# SuperPro.net
KiCad netlist of a schematic drawn in EAGLE
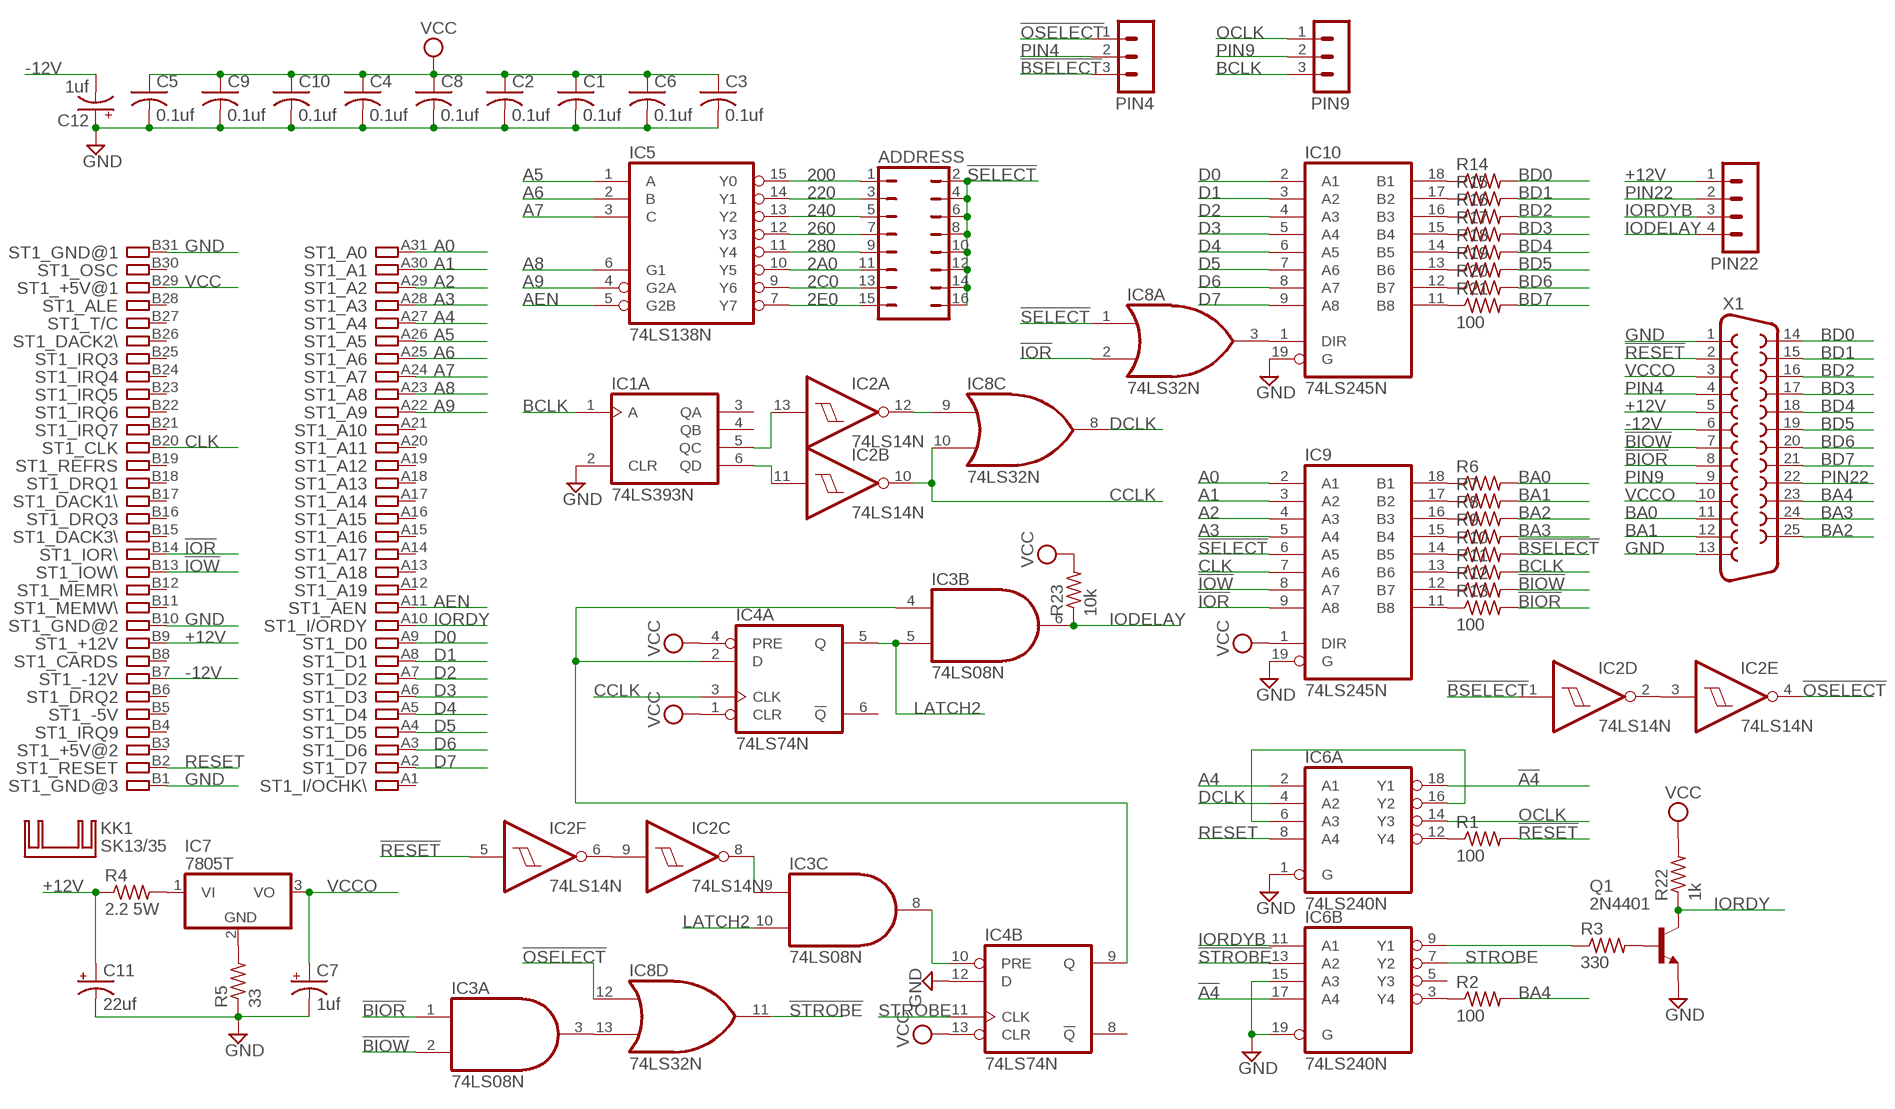
[diagram p0: schematic, sheet 1]

(export (version "E")
  (design (tool "Eeschema 10.0.6"))
  (components
    (comp (ref "ADDRESS")
      (value "JP8Q")
      (footprint "eagle-import:JP8Q")
      (libsource (lib "eagle-import") (part "JP8Q"))
    )
    (comp (ref "C1")
      (value "0.1uf")
      (footprint "eagle-import:C050-025X075")
      (libsource (lib "eagle-import") (part "C-US050-025X075"))
    )
    (comp (ref "C2")
      (value "0.1uf")
      (footprint "eagle-import:C050-025X075")
      (libsource (lib "eagle-import") (part "C-US050-025X075"))
    )
    (comp (ref "C3")
      (value "0.1uf")
      (footprint "eagle-import:C050-025X075")
      (libsource (lib "eagle-import") (part "C-US050-025X075"))
    )
    (comp (ref "C4")
      (value "0.1uf")
      (footprint "eagle-import:C050-025X075")
      (libsource (lib "eagle-import") (part "C-US050-025X075"))
    )
    (comp (ref "C5")
      (value "0.1uf")
      (footprint "eagle-import:C050-025X075")
      (libsource (lib "eagle-import") (part "C-US050-025X075"))
    )
    (comp (ref "C6")
      (value "0.1uf")
      (footprint "eagle-import:C050-025X075")
      (libsource (lib "eagle-import") (part "C-US050-025X075"))
    )
    (comp (ref "C7")
      (value "1uf")
      (footprint "eagle-import:E5-10,5")
      (libsource (lib "eagle-import") (part "CPOL-USE5-10.5"))
    )
    (comp (ref "C8")
      (value "0.1uf")
      (footprint "eagle-import:C050-025X075")
      (libsource (lib "eagle-import") (part "C-US050-025X075"))
    )
    (comp (ref "C9")
      (value "0.1uf")
      (footprint "eagle-import:C050-025X075")
      (libsource (lib "eagle-import") (part "C-US050-025X075"))
    )
    (comp (ref "C10")
      (value "0.1uf")
      (footprint "eagle-import:C050-025X075")
      (libsource (lib "eagle-import") (part "C-US050-025X075"))
    )
    (comp (ref "C11")
      (value "22uf")
      (footprint "eagle-import:E5-10,5")
      (libsource (lib "eagle-import") (part "CPOL-USE5-10.5"))
    )
    (comp (ref "C12")
      (value "1uf")
      (footprint "eagle-import:E5-10,5")
      (libsource (lib "eagle-import") (part "CPOL-USE5-10.5"))
    )
    (comp (ref "IC1")
      (value "74LS393N")
      (footprint "eagle-import:DIL14")
      (libsource (lib "eagle-import") (part "74393NLS"))
    )
    (comp (ref "IC2")
      (value "74LS14N")
      (footprint "eagle-import:DIL14")
      (libsource (lib "eagle-import") (part "7414NLS"))
    )
    (comp (ref "IC3")
      (value "74LS08N")
      (footprint "eagle-import:DIL14")
      (libsource (lib "eagle-import") (part "7408NLS"))
    )
    (comp (ref "IC4")
      (value "74LS74N")
      (footprint "eagle-import:DIL14")
      (libsource (lib "eagle-import") (part "7474NLS"))
    )
    (comp (ref "IC5")
      (value "74LS138N")
      (footprint "eagle-import:DIL16")
      (libsource (lib "eagle-import") (part "74138NLS"))
    )
    (comp (ref "IC6")
      (value "74LS240N")
      (footprint "eagle-import:DIL20")
      (libsource (lib "eagle-import") (part "74240NLS"))
    )
    (comp (ref "IC7")
      (value "7805T")
      (footprint "eagle-import:TO220H")
      (libsource (lib "eagle-import") (part "78T05"))
    )
    (comp (ref "IC8")
      (value "74LS32N")
      (footprint "eagle-import:DIL14")
      (libsource (lib "eagle-import") (part "7432NLS"))
    )
    (comp (ref "IC9")
      (value "74LS245N")
      (footprint "eagle-import:DIL20")
      (libsource (lib "eagle-import") (part "74245NLS"))
    )
    (comp (ref "IC10")
      (value "74LS245N")
      (footprint "eagle-import:DIL20")
      (libsource (lib "eagle-import") (part "74245NLS"))
    )
    (comp (ref "KK1")
      (value "SK13/35")
      (footprint "eagle-import:SK13_35")
      (libsource (lib "eagle-import") (part "SK13/35"))
    )
    (comp (ref "PIN4")
      (value "MA03-1")
      (footprint "eagle-import:MA03-1")
      (libsource (lib "eagle-import") (part "MA03-1"))
    )
    (comp (ref "PIN9")
      (value "MA03-1")
      (footprint "eagle-import:MA03-1")
      (libsource (lib "eagle-import") (part "MA03-1"))
    )
    (comp (ref "PIN22")
      (value "MA04-1")
      (footprint "eagle-import:MA04-1")
      (libsource (lib "eagle-import") (part "MA04-1"))
    )
    (comp (ref "Q1")
      (value "2N4401")
      (footprint "eagle-import:TO92")
      (libsource (lib "eagle-import") (part "2N4416"))
    )
    (comp (ref "R1")
      (value "100")
      (footprint "eagle-import:0207_10")
      (libsource (lib "eagle-import") (part "R-US_0207/10"))
    )
    (comp (ref "R2")
      (value "100")
      (footprint "eagle-import:0207_10")
      (libsource (lib "eagle-import") (part "R-US_0207/10"))
    )
    (comp (ref "R3")
      (value "330")
      (footprint "eagle-import:0207_10")
      (libsource (lib "eagle-import") (part "R-US_0207/10"))
    )
    (comp (ref "R4")
      (value "2.2 5W")
      (footprint "eagle-import:0922_22")
      (libsource (lib "eagle-import") (part "R-US_0922/22"))
    )
    (comp (ref "R5")
      (value "33")
      (footprint "eagle-import:0207_10")
      (libsource (lib "eagle-import") (part "R-US_0207/10"))
    )
    (comp (ref "R6")
      (value "R-US_0207/10")
      (footprint "eagle-import:0207_10")
      (libsource (lib "eagle-import") (part "R-US_0207/10"))
    )
    (comp (ref "R7")
      (value "R-US_0207/10")
      (footprint "eagle-import:0207_10")
      (libsource (lib "eagle-import") (part "R-US_0207/10"))
    )
    (comp (ref "R8")
      (value "R-US_0207/10")
      (footprint "eagle-import:0207_10")
      (libsource (lib "eagle-import") (part "R-US_0207/10"))
    )
    (comp (ref "R9")
      (value "R-US_0207/10")
      (footprint "eagle-import:0207_10")
      (libsource (lib "eagle-import") (part "R-US_0207/10"))
    )
    (comp (ref "R10")
      (value "R-US_0207/10")
      (footprint "eagle-import:0207_10")
      (libsource (lib "eagle-import") (part "R-US_0207/10"))
    )
    (comp (ref "R11")
      (value "R-US_0207/10")
      (footprint "eagle-import:0207_10")
      (libsource (lib "eagle-import") (part "R-US_0207/10"))
    )
    (comp (ref "R12")
      (value "R-US_0207/10")
      (footprint "eagle-import:0207_10")
      (libsource (lib "eagle-import") (part "R-US_0207/10"))
    )
    (comp (ref "R13")
      (value "100")
      (footprint "eagle-import:0207_10")
      (libsource (lib "eagle-import") (part "R-US_0207/10"))
    )
    (comp (ref "R14")
      (value "R-US_0207/10")
      (footprint "eagle-import:0207_10")
      (libsource (lib "eagle-import") (part "R-US_0207/10"))
    )
    (comp (ref "R15")
      (value "R-US_0207/10")
      (footprint "eagle-import:0207_10")
      (libsource (lib "eagle-import") (part "R-US_0207/10"))
    )
    (comp (ref "R16")
      (value "R-US_0207/10")
      (footprint "eagle-import:0207_10")
      (libsource (lib "eagle-import") (part "R-US_0207/10"))
    )
    (comp (ref "R17")
      (value "R-US_0207/10")
      (footprint "eagle-import:0207_10")
      (libsource (lib "eagle-import") (part "R-US_0207/10"))
    )
    (comp (ref "R18")
      (value "R-US_0207/10")
      (footprint "eagle-import:0207_10")
      (libsource (lib "eagle-import") (part "R-US_0207/10"))
    )
    (comp (ref "R19")
      (value "R-US_0207/10")
      (footprint "eagle-import:0207_10")
      (libsource (lib "eagle-import") (part "R-US_0207/10"))
    )
    (comp (ref "R20")
      (value "R-US_0207/10")
      (footprint "eagle-import:0207_10")
      (libsource (lib "eagle-import") (part "R-US_0207/10"))
    )
    (comp (ref "R21")
      (value "100")
      (footprint "eagle-import:0207_10")
      (libsource (lib "eagle-import") (part "R-US_0207/10"))
    )
    (comp (ref "R22")
      (value "1k")
      (footprint "eagle-import:0207_10")
      (libsource (lib "eagle-import") (part "R-US_0207/10"))
    )
    (comp (ref "R23")
      (value "10k")
      (footprint "eagle-import:0207_10")
      (libsource (lib "eagle-import") (part "R-US_0207/10"))
    )
    (comp (ref "ST1")
      (value "IBM8BIT")
      (footprint "eagle-import:IBM8BIT")
      (libsource (lib "eagle-import") (part "IBM8BIT"))
    )
    (comp (ref "X1")
      (value "F25H")
      (footprint "eagle-import:F25H")
      (libsource (lib "eagle-import") (part "F25H"))
    )
  )
  (nets
    (net (code "1") (name "/+12V") (class "Default")
      (node (ref "C11") (pin "+") (pinfunction "+_+") (pintype "passive"))
      (node (ref "PIN22") (pin "1") (pinfunction "1_1") (pintype "passive"))
      (node (ref "R4") (pin "1") (pinfunction "1_1") (pintype "passive"))
      (node (ref "ST1") (pin "B9") (pinfunction "P_B9") (pintype "bidirectional"))
      (node (ref "X1") (pin "5") (pinfunction "5_5") (pintype "passive"))
    )
    (net (code "2") (name "/-12V") (class "Default")
      (node (ref "C12") (pin "-") (pinfunction "-_-") (pintype "passive"))
      (node (ref "ST1") (pin "B7") (pinfunction "P_B7") (pintype "bidirectional"))
      (node (ref "X1") (pin "6") (pinfunction "6_6") (pintype "passive"))
    )
    (net (code "3") (name "/2A0") (class "Default")
      (node (ref "ADDRESS") (pin "11") (pinfunction "11_11") (pintype "passive"))
      (node (ref "IC5") (pin "10") (pinfunction "Y5_10") (pintype "output"))
    )
    (net (code "4") (name "/2C0") (class "Default")
      (node (ref "ADDRESS") (pin "13") (pinfunction "13_13") (pintype "passive"))
      (node (ref "IC5") (pin "9") (pinfunction "Y6_9") (pintype "output"))
    )
    (net (code "5") (name "/2E0") (class "Default")
      (node (ref "ADDRESS") (pin "15") (pinfunction "15_15") (pintype "passive"))
      (node (ref "IC5") (pin "7") (pinfunction "Y7_7") (pintype "output"))
    )
    (net (code "6") (name "/200") (class "Default")
      (node (ref "ADDRESS") (pin "1") (pinfunction "1_1") (pintype "passive"))
      (node (ref "IC5") (pin "15") (pinfunction "Y0_15") (pintype "output"))
    )
    (net (code "7") (name "/220") (class "Default")
      (node (ref "ADDRESS") (pin "3") (pinfunction "3_3") (pintype "passive"))
      (node (ref "IC5") (pin "14") (pinfunction "Y1_14") (pintype "output"))
    )
    (net (code "8") (name "/240") (class "Default")
      (node (ref "ADDRESS") (pin "5") (pinfunction "5_5") (pintype "passive"))
      (node (ref "IC5") (pin "13") (pinfunction "Y2_13") (pintype "output"))
    )
    (net (code "9") (name "/260") (class "Default")
      (node (ref "ADDRESS") (pin "7") (pinfunction "7_7") (pintype "passive"))
      (node (ref "IC5") (pin "12") (pinfunction "Y3_12") (pintype "output"))
    )
    (net (code "10") (name "/280") (class "Default")
      (node (ref "ADDRESS") (pin "9") (pinfunction "9_9") (pintype "passive"))
      (node (ref "IC5") (pin "11") (pinfunction "Y4_11") (pintype "output"))
    )
    (net (code "11") (name "/A0") (class "Default")
      (node (ref "IC9") (pin "2") (pinfunction "A1_2") (pintype "bidirectional"))
      (node (ref "ST1") (pin "A31") (pinfunction "P_A31") (pintype "bidirectional"))
    )
    (net (code "12") (name "/A1") (class "Default")
      (node (ref "IC9") (pin "3") (pinfunction "A2_3") (pintype "bidirectional"))
      (node (ref "ST1") (pin "A30") (pinfunction "P_A30") (pintype "bidirectional"))
    )
    (net (code "13") (name "/A2") (class "Default")
      (node (ref "IC9") (pin "4") (pinfunction "A3_4") (pintype "bidirectional"))
      (node (ref "ST1") (pin "A29") (pinfunction "P_A29") (pintype "bidirectional"))
    )
    (net (code "14") (name "/A3") (class "Default")
      (node (ref "IC9") (pin "5") (pinfunction "A4_5") (pintype "bidirectional"))
      (node (ref "ST1") (pin "A28") (pinfunction "P_A28") (pintype "bidirectional"))
    )
    (net (code "15") (name "/A4") (class "Default")
      (node (ref "IC6") (pin "2") (pinfunction "A1_2") (pintype "input"))
      (node (ref "ST1") (pin "A27") (pinfunction "P_A27") (pintype "bidirectional"))
    )
    (net (code "16") (name "/A5") (class "Default")
      (node (ref "IC5") (pin "1") (pinfunction "A_1") (pintype "input"))
      (node (ref "ST1") (pin "A26") (pinfunction "P_A26") (pintype "bidirectional"))
    )
    (net (code "17") (name "/A6") (class "Default")
      (node (ref "IC5") (pin "2") (pinfunction "B_2") (pintype "input"))
      (node (ref "ST1") (pin "A25") (pinfunction "P_A25") (pintype "bidirectional"))
    )
    (net (code "18") (name "/A7") (class "Default")
      (node (ref "IC5") (pin "3") (pinfunction "C_3") (pintype "input"))
      (node (ref "ST1") (pin "A24") (pinfunction "P_A24") (pintype "bidirectional"))
    )
    (net (code "19") (name "/A8") (class "Default")
      (node (ref "IC5") (pin "6") (pinfunction "G1_6") (pintype "input"))
      (node (ref "ST1") (pin "A23") (pinfunction "P_A23") (pintype "bidirectional"))
    )
    (net (code "20") (name "/A9") (class "Default")
      (node (ref "IC5") (pin "4") (pinfunction "G2A_4") (pintype "input"))
      (node (ref "ST1") (pin "A22") (pinfunction "P_A22") (pintype "bidirectional"))
    )
    (net (code "21") (name "/AEN") (class "Default")
      (node (ref "IC5") (pin "5") (pinfunction "G2B_5") (pintype "input"))
      (node (ref "ST1") (pin "A11") (pinfunction "P_A11") (pintype "bidirectional"))
    )
    (net (code "22") (name "/BA0") (class "Default")
      (node (ref "R6") (pin "2") (pinfunction "2_2") (pintype "passive"))
      (node (ref "X1") (pin "11") (pinfunction "11_11") (pintype "passive"))
    )
    (net (code "23") (name "/BA1") (class "Default")
      (node (ref "R7") (pin "2") (pinfunction "2_2") (pintype "passive"))
      (node (ref "X1") (pin "12") (pinfunction "12_12") (pintype "passive"))
    )
    (net (code "24") (name "/BA2") (class "Default")
      (node (ref "R8") (pin "2") (pinfunction "2_2") (pintype "passive"))
      (node (ref "X1") (pin "25") (pinfunction "25_25") (pintype "passive"))
    )
    (net (code "25") (name "/BA3") (class "Default")
      (node (ref "R9") (pin "2") (pinfunction "2_2") (pintype "passive"))
      (node (ref "X1") (pin "24") (pinfunction "24_24") (pintype "passive"))
    )
    (net (code "26") (name "/BA4") (class "Default")
      (node (ref "R2") (pin "2") (pinfunction "2_2") (pintype "passive"))
      (node (ref "X1") (pin "23") (pinfunction "23_23") (pintype "passive"))
    )
    (net (code "27") (name "/BCLK") (class "Default")
      (node (ref "IC1") (pin "1") (pinfunction "A_1") (pintype "input"))
      (node (ref "PIN9") (pin "3") (pinfunction "3_3") (pintype "passive"))
      (node (ref "R11") (pin "2") (pinfunction "2_2") (pintype "passive"))
    )
    (net (code "28") (name "/BD0") (class "Default")
      (node (ref "R14") (pin "2") (pinfunction "2_2") (pintype "passive"))
      (node (ref "X1") (pin "14") (pinfunction "14_14") (pintype "passive"))
    )
    (net (code "29") (name "/BD1") (class "Default")
      (node (ref "R15") (pin "2") (pinfunction "2_2") (pintype "passive"))
      (node (ref "X1") (pin "15") (pinfunction "15_15") (pintype "passive"))
    )
    (net (code "30") (name "/BD2") (class "Default")
      (node (ref "R16") (pin "2") (pinfunction "2_2") (pintype "passive"))
      (node (ref "X1") (pin "16") (pinfunction "16_16") (pintype "passive"))
    )
    (net (code "31") (name "/BD3") (class "Default")
      (node (ref "R17") (pin "2") (pinfunction "2_2") (pintype "passive"))
      (node (ref "X1") (pin "17") (pinfunction "17_17") (pintype "passive"))
    )
    (net (code "32") (name "/BD4") (class "Default")
      (node (ref "R18") (pin "2") (pinfunction "2_2") (pintype "passive"))
      (node (ref "X1") (pin "18") (pinfunction "18_18") (pintype "passive"))
    )
    (net (code "33") (name "/BD5") (class "Default")
      (node (ref "R19") (pin "2") (pinfunction "2_2") (pintype "passive"))
      (node (ref "X1") (pin "19") (pinfunction "19_19") (pintype "passive"))
    )
    (net (code "34") (name "/BD6") (class "Default")
      (node (ref "R20") (pin "2") (pinfunction "2_2") (pintype "passive"))
      (node (ref "X1") (pin "20") (pinfunction "20_20") (pintype "passive"))
    )
    (net (code "35") (name "/BD7") (class "Default")
      (node (ref "R21") (pin "2") (pinfunction "2_2") (pintype "passive"))
      (node (ref "X1") (pin "21") (pinfunction "21_21") (pintype "passive"))
    )
    (net (code "36") (name "/CCLK") (class "Default")
      (node (ref "IC2") (pin "10") (pinfunction "O_10") (pintype "output"))
      (node (ref "IC4") (pin "3") (pinfunction "CLK_3") (pintype "input"))
      (node (ref "IC8") (pin "10") (pinfunction "I1_10") (pintype "input"))
    )
    (net (code "37") (name "/CLK") (class "Default")
      (node (ref "IC9") (pin "7") (pinfunction "A6_7") (pintype "bidirectional"))
      (node (ref "ST1") (pin "B20") (pinfunction "P_B20") (pintype "bidirectional"))
    )
    (net (code "38") (name "/D0") (class "Default")
      (node (ref "IC10") (pin "2") (pinfunction "A1_2") (pintype "bidirectional"))
      (node (ref "ST1") (pin "A9") (pinfunction "P_A9") (pintype "bidirectional"))
    )
    (net (code "39") (name "/D1") (class "Default")
      (node (ref "IC10") (pin "3") (pinfunction "A2_3") (pintype "bidirectional"))
      (node (ref "ST1") (pin "A8") (pinfunction "P_A8") (pintype "bidirectional"))
    )
    (net (code "40") (name "/D2") (class "Default")
      (node (ref "IC10") (pin "4") (pinfunction "A3_4") (pintype "bidirectional"))
      (node (ref "ST1") (pin "A7") (pinfunction "P_A7") (pintype "bidirectional"))
    )
    (net (code "41") (name "/D3") (class "Default")
      (node (ref "IC10") (pin "5") (pinfunction "A4_5") (pintype "bidirectional"))
      (node (ref "ST1") (pin "A6") (pinfunction "P_A6") (pintype "bidirectional"))
    )
    (net (code "42") (name "/D4") (class "Default")
      (node (ref "IC10") (pin "6") (pinfunction "A5_6") (pintype "bidirectional"))
      (node (ref "ST1") (pin "A5") (pinfunction "P_A5") (pintype "bidirectional"))
    )
    (net (code "43") (name "/D5") (class "Default")
      (node (ref "IC10") (pin "7") (pinfunction "A6_7") (pintype "bidirectional"))
      (node (ref "ST1") (pin "A4") (pinfunction "P_A4") (pintype "bidirectional"))
    )
    (net (code "44") (name "/D6") (class "Default")
      (node (ref "IC10") (pin "8") (pinfunction "A7_8") (pintype "bidirectional"))
      (node (ref "ST1") (pin "A3") (pinfunction "P_A3") (pintype "bidirectional"))
    )
    (net (code "45") (name "/D7") (class "Default")
      (node (ref "IC10") (pin "9") (pinfunction "A8_9") (pintype "bidirectional"))
      (node (ref "ST1") (pin "A2") (pinfunction "P_A2") (pintype "bidirectional"))
    )
    (net (code "46") (name "/DCLK") (class "Default")
      (node (ref "IC6") (pin "4") (pinfunction "A2_4") (pintype "input"))
      (node (ref "IC8") (pin "8") (pinfunction "O_8") (pintype "output"))
    )
    (net (code "47") (name "/IODELAY") (class "Default")
      (node (ref "IC3") (pin "6") (pinfunction "O_6") (pintype "output"))
      (node (ref "PIN22") (pin "4") (pinfunction "4_4") (pintype "passive"))
      (node (ref "R23") (pin "1") (pinfunction "1_1") (pintype "passive"))
    )
    (net (code "48") (name "/IORDY") (class "Default")
      (node (ref "Q1") (pin "1") (pinfunction "C_1") (pintype "passive"))
      (node (ref "R22") (pin "1") (pinfunction "1_1") (pintype "passive"))
      (node (ref "ST1") (pin "A10") (pinfunction "P_A10") (pintype "bidirectional"))
    )
    (net (code "49") (name "/IORDYB") (class "Default")
      (node (ref "IC6") (pin "11") (pinfunction "A1_11") (pintype "input"))
      (node (ref "PIN22") (pin "3") (pinfunction "3_3") (pintype "passive"))
    )
    (net (code "50") (name "/LATCH2") (class "Default")
      (node (ref "IC3") (pin "10") (pinfunction "I1_10") (pintype "input"))
      (node (ref "IC3") (pin "5") (pinfunction "I1_5") (pintype "input"))
      (node (ref "IC4") (pin "5") (pinfunction "Q_5") (pintype "output"))
    )
    (net (code "51") (name "/OCLK") (class "Default")
      (node (ref "IC6") (pin "14") (pinfunction "Y3_14") (pintype "tri_state"))
      (node (ref "PIN9") (pin "1") (pinfunction "1_1") (pintype "passive"))
    )
    (net (code "52") (name "/PIN4") (class "Default")
      (node (ref "PIN4") (pin "2") (pinfunction "2_2") (pintype "passive"))
      (node (ref "X1") (pin "4") (pinfunction "4_4") (pintype "passive"))
    )
    (net (code "53") (name "/PIN9") (class "Default")
      (node (ref "PIN9") (pin "2") (pinfunction "2_2") (pintype "passive"))
      (node (ref "X1") (pin "9") (pinfunction "9_9") (pintype "passive"))
    )
    (net (code "54") (name "/PIN22") (class "Default")
      (node (ref "PIN22") (pin "2") (pinfunction "2_2") (pintype "passive"))
      (node (ref "X1") (pin "22") (pinfunction "22_22") (pintype "passive"))
    )
    (net (code "55") (name "/RESET") (class "Default")
      (node (ref "IC6") (pin "8") (pinfunction "A4_8") (pintype "input"))
      (node (ref "ST1") (pin "B2") (pinfunction "P_B2") (pintype "bidirectional"))
    )
    (net (code "56") (name "/STROBE") (class "Default")
      (node (ref "IC4") (pin "11") (pinfunction "CLK_11") (pintype "input"))
      (node (ref "IC6") (pin "7") (pinfunction "Y2_7") (pintype "tri_state"))
    )
    (net (code "57") (name "/VCCO") (class "Default")
      (node (ref "C7") (pin "+") (pinfunction "+_+") (pintype "passive"))
      (node (ref "IC7") (pin "3") (pinfunction "VO_3") (pintype "passive"))
      (node (ref "X1") (pin "10") (pinfunction "10_10") (pintype "passive"))
      (node (ref "X1") (pin "3") (pinfunction "3_3") (pintype "passive"))
    )
    (net (code "58") (name "/~{A4}") (class "Default")
      (node (ref "IC6") (pin "17") (pinfunction "A4_17") (pintype "input"))
      (node (ref "IC6") (pin "18") (pinfunction "Y1_18") (pintype "tri_state"))
    )
    (net (code "59") (name "/~{BIOR}") (class "Default")
      (node (ref "IC3") (pin "1") (pinfunction "I0_1") (pintype "input"))
      (node (ref "R13") (pin "2") (pinfunction "2_2") (pintype "passive"))
      (node (ref "X1") (pin "8") (pinfunction "8_8") (pintype "passive"))
    )
    (net (code "60") (name "/~{BIOW}") (class "Default")
      (node (ref "IC3") (pin "2") (pinfunction "I1_2") (pintype "input"))
      (node (ref "R12") (pin "2") (pinfunction "2_2") (pintype "passive"))
      (node (ref "X1") (pin "7") (pinfunction "7_7") (pintype "passive"))
    )
    (net (code "61") (name "/~{BSELECT}") (class "Default")
      (node (ref "IC2") (pin "1") (pinfunction "I_1") (pintype "input"))
      (node (ref "PIN4") (pin "3") (pinfunction "3_3") (pintype "passive"))
      (node (ref "R10") (pin "2") (pinfunction "2_2") (pintype "passive"))
    )
    (net (code "62") (name "/~{IOR}") (class "Default")
      (node (ref "IC8") (pin "2") (pinfunction "I1_2") (pintype "input"))
      (node (ref "IC9") (pin "9") (pinfunction "A8_9") (pintype "bidirectional"))
      (node (ref "ST1") (pin "B14") (pinfunction "P_B14") (pintype "bidirectional"))
    )
    (net (code "63") (name "/~{IOW}") (class "Default")
      (node (ref "IC9") (pin "8") (pinfunction "A7_8") (pintype "bidirectional"))
      (node (ref "ST1") (pin "B13") (pinfunction "P_B13") (pintype "bidirectional"))
    )
    (net (code "64") (name "/~{OSELECT}") (class "Default")
      (node (ref "IC2") (pin "4") (pinfunction "O_4") (pintype "output"))
      (node (ref "IC8") (pin "12") (pinfunction "I0_12") (pintype "input"))
      (node (ref "PIN4") (pin "1") (pinfunction "1_1") (pintype "passive"))
    )
    (net (code "65") (name "/~{RESET}") (class "Default")
      (node (ref "IC2") (pin "5") (pinfunction "I_5") (pintype "input"))
      (node (ref "R1") (pin "2") (pinfunction "2_2") (pintype "passive"))
      (node (ref "X1") (pin "2") (pinfunction "2_2") (pintype "passive"))
    )
    (net (code "66") (name "/~{SELECT}") (class "Default")
      (node (ref "ADDRESS") (pin "10") (pinfunction "10_10") (pintype "passive"))
      (node (ref "ADDRESS") (pin "12") (pinfunction "12_12") (pintype "passive"))
      (node (ref "ADDRESS") (pin "14") (pinfunction "14_14") (pintype "passive"))
      (node (ref "ADDRESS") (pin "16") (pinfunction "16_16") (pintype "passive"))
      (node (ref "ADDRESS") (pin "2") (pinfunction "2_2") (pintype "passive"))
      (node (ref "ADDRESS") (pin "4") (pinfunction "4_4") (pintype "passive"))
      (node (ref "ADDRESS") (pin "6") (pinfunction "6_6") (pintype "passive"))
      (node (ref "ADDRESS") (pin "8") (pinfunction "8_8") (pintype "passive"))
      (node (ref "IC8") (pin "1") (pinfunction "I0_1") (pintype "input"))
      (node (ref "IC9") (pin "6") (pinfunction "A5_6") (pintype "bidirectional"))
    )
    (net (code "67") (name "/~{STROBE}") (class "Default")
      (node (ref "IC6") (pin "13") (pinfunction "A2_13") (pintype "input"))
      (node (ref "IC8") (pin "11") (pinfunction "O_11") (pintype "output"))
    )
    (net (code "68") (name "GND") (class "Default")
      (node (ref "C1") (pin "2") (pinfunction "2_2") (pintype "passive"))
      (node (ref "C10") (pin "2") (pinfunction "2_2") (pintype "passive"))
      (node (ref "C11") (pin "-") (pinfunction "-_-") (pintype "passive"))
      (node (ref "C12") (pin "+") (pinfunction "+_+") (pintype "passive"))
      (node (ref "C2") (pin "2") (pinfunction "2_2") (pintype "passive"))
      (node (ref "C3") (pin "2") (pinfunction "2_2") (pintype "passive"))
      (node (ref "C4") (pin "2") (pinfunction "2_2") (pintype "passive"))
      (node (ref "C5") (pin "2") (pinfunction "2_2") (pintype "passive"))
      (node (ref "C6") (pin "2") (pinfunction "2_2") (pintype "passive"))
      (node (ref "C7") (pin "-") (pinfunction "-_-") (pintype "passive"))
      (node (ref "C8") (pin "2") (pinfunction "2_2") (pintype "passive"))
      (node (ref "C9") (pin "2") (pinfunction "2_2") (pintype "passive"))
      (node (ref "IC1") (pin "2") (pinfunction "CLR_2") (pintype "input"))
      (node (ref "IC10") (pin "19") (pinfunction "G_19") (pintype "input"))
      (node (ref "IC4") (pin "12") (pinfunction "D_12") (pintype "input"))
      (node (ref "IC6") (pin "1") (pinfunction "G_1") (pintype "input"))
      (node (ref "IC6") (pin "15") (pinfunction "A3_15") (pintype "input"))
      (node (ref "IC6") (pin "19") (pinfunction "G_19") (pintype "input"))
      (node (ref "IC9") (pin "19") (pinfunction "G_19") (pintype "input"))
      (node (ref "Q1") (pin "3") (pinfunction "E_3") (pintype "passive"))
      (node (ref "R5") (pin "1") (pinfunction "1_1") (pintype "passive"))
      (node (ref "ST1") (pin "B1") (pinfunction "P_B1") (pintype "bidirectional"))
      (node (ref "ST1") (pin "B10") (pinfunction "P_B10") (pintype "bidirectional"))
      (node (ref "ST1") (pin "B31") (pinfunction "P_B31") (pintype "bidirectional"))
      (node (ref "X1") (pin "1") (pinfunction "1_1") (pintype "passive"))
      (node (ref "X1") (pin "13") (pinfunction "13_13") (pintype "passive"))
    )
    (net (code "69") (name "Net-(IC1A-QC)") (class "Default")
      (node (ref "IC1") (pin "5") (pinfunction "QC_5") (pintype "output"))
      (node (ref "IC2") (pin "13") (pinfunction "I_13") (pintype "input"))
    )
    (net (code "70") (name "Net-(IC1A-QD)") (class "Default")
      (node (ref "IC1") (pin "6") (pinfunction "QD_6") (pintype "output"))
      (node (ref "IC2") (pin "11") (pinfunction "I_11") (pintype "input"))
    )
    (net (code "71") (name "Net-(IC2A-O)") (class "Default")
      (node (ref "IC2") (pin "12") (pinfunction "O_12") (pintype "output"))
      (node (ref "IC8") (pin "9") (pinfunction "I0_9") (pintype "input"))
    )
    (net (code "72") (name "Net-(IC2C-I)") (class "Default")
      (node (ref "IC2") (pin "6") (pinfunction "O_6") (pintype "output"))
      (node (ref "IC2") (pin "9") (pinfunction "I_9") (pintype "input"))
    )
    (net (code "73") (name "Net-(IC2C-O)") (class "Default")
      (node (ref "IC2") (pin "8") (pinfunction "O_8") (pintype "output"))
      (node (ref "IC3") (pin "9") (pinfunction "I0_9") (pintype "input"))
    )
    (net (code "74") (name "Net-(IC2D-O)") (class "Default")
      (node (ref "IC2") (pin "2") (pinfunction "O_2") (pintype "output"))
      (node (ref "IC2") (pin "3") (pinfunction "I_3") (pintype "input"))
    )
    (net (code "75") (name "Net-(IC3A-O)") (class "Default")
      (node (ref "IC3") (pin "3") (pinfunction "O_3") (pintype "output"))
      (node (ref "IC8") (pin "13") (pinfunction "I1_13") (pintype "input"))
    )
    (net (code "76") (name "Net-(IC3B-I0)") (class "Default")
      (node (ref "IC3") (pin "4") (pinfunction "I0_4") (pintype "input"))
      (node (ref "IC4") (pin "2") (pinfunction "D_2") (pintype "input"))
      (node (ref "IC4") (pin "9") (pinfunction "Q_9") (pintype "output"))
    )
    (net (code "77") (name "Net-(IC3C-O)") (class "Default")
      (node (ref "IC3") (pin "8") (pinfunction "O_8") (pintype "output"))
      (node (ref "IC4") (pin "10") (pinfunction "PRE_10") (pintype "input"))
    )
    (net (code "78") (name "Net-(IC6A-A3)") (class "Default")
      (node (ref "IC6") (pin "16") (pinfunction "Y2_16") (pintype "tri_state"))
      (node (ref "IC6") (pin "6") (pinfunction "A3_6") (pintype "input"))
    )
    (net (code "79") (name "Net-(IC6A-Y4)") (class "Default")
      (node (ref "IC6") (pin "12") (pinfunction "Y4_12") (pintype "tri_state"))
      (node (ref "R1") (pin "1") (pinfunction "1_1") (pintype "passive"))
    )
    (net (code "80") (name "Net-(IC6B-Y1)") (class "Default")
      (node (ref "IC6") (pin "9") (pinfunction "Y1_9") (pintype "tri_state"))
      (node (ref "R3") (pin "1") (pinfunction "1_1") (pintype "passive"))
    )
    (net (code "81") (name "Net-(IC6B-Y4)") (class "Default")
      (node (ref "IC6") (pin "3") (pinfunction "Y4_3") (pintype "tri_state"))
      (node (ref "R2") (pin "1") (pinfunction "1_1") (pintype "passive"))
    )
    (net (code "82") (name "Net-(IC7-GND)") (class "Default")
      (node (ref "IC7") (pin "2") (pinfunction "GND_2") (pintype "passive"))
      (node (ref "R5") (pin "2") (pinfunction "2_2") (pintype "passive"))
    )
    (net (code "83") (name "Net-(IC7-VI)") (class "Default")
      (node (ref "IC7") (pin "1") (pinfunction "VI_1") (pintype "input"))
      (node (ref "R4") (pin "2") (pinfunction "2_2") (pintype "passive"))
    )
    (net (code "84") (name "Net-(IC9A-B1)") (class "Default")
      (node (ref "IC9") (pin "18") (pinfunction "B1_18") (pintype "bidirectional"))
      (node (ref "R6") (pin "1") (pinfunction "1_1") (pintype "passive"))
    )
    (net (code "85") (name "Net-(IC9A-B2)") (class "Default")
      (node (ref "IC9") (pin "17") (pinfunction "B2_17") (pintype "bidirectional"))
      (node (ref "R7") (pin "1") (pinfunction "1_1") (pintype "passive"))
    )
    (net (code "86") (name "Net-(IC9A-B3)") (class "Default")
      (node (ref "IC9") (pin "16") (pinfunction "B3_16") (pintype "bidirectional"))
      (node (ref "R8") (pin "1") (pinfunction "1_1") (pintype "passive"))
    )
    (net (code "87") (name "Net-(IC9A-B4)") (class "Default")
      (node (ref "IC9") (pin "15") (pinfunction "B4_15") (pintype "bidirectional"))
      (node (ref "R9") (pin "1") (pinfunction "1_1") (pintype "passive"))
    )
    (net (code "88") (name "Net-(IC9A-B5)") (class "Default")
      (node (ref "IC9") (pin "14") (pinfunction "B5_14") (pintype "bidirectional"))
      (node (ref "R10") (pin "1") (pinfunction "1_1") (pintype "passive"))
    )
    (net (code "89") (name "Net-(IC9A-B6)") (class "Default")
      (node (ref "IC9") (pin "13") (pinfunction "B6_13") (pintype "bidirectional"))
      (node (ref "R11") (pin "1") (pinfunction "1_1") (pintype "passive"))
    )
    (net (code "90") (name "Net-(IC9A-B7)") (class "Default")
      (node (ref "IC9") (pin "12") (pinfunction "B7_12") (pintype "bidirectional"))
      (node (ref "R12") (pin "1") (pinfunction "1_1") (pintype "passive"))
    )
    (net (code "91") (name "Net-(IC9A-B8)") (class "Default")
      (node (ref "IC9") (pin "11") (pinfunction "B8_11") (pintype "bidirectional"))
      (node (ref "R13") (pin "1") (pinfunction "1_1") (pintype "passive"))
    )
    (net (code "92") (name "Net-(IC10A-B1)") (class "Default")
      (node (ref "IC10") (pin "18") (pinfunction "B1_18") (pintype "bidirectional"))
      (node (ref "R14") (pin "1") (pinfunction "1_1") (pintype "passive"))
    )
    (net (code "93") (name "Net-(IC10A-B2)") (class "Default")
      (node (ref "IC10") (pin "17") (pinfunction "B2_17") (pintype "bidirectional"))
      (node (ref "R15") (pin "1") (pinfunction "1_1") (pintype "passive"))
    )
    (net (code "94") (name "Net-(IC10A-B3)") (class "Default")
      (node (ref "IC10") (pin "16") (pinfunction "B3_16") (pintype "bidirectional"))
      (node (ref "R16") (pin "1") (pinfunction "1_1") (pintype "passive"))
    )
    (net (code "95") (name "Net-(IC10A-B4)") (class "Default")
      (node (ref "IC10") (pin "15") (pinfunction "B4_15") (pintype "bidirectional"))
      (node (ref "R17") (pin "1") (pinfunction "1_1") (pintype "passive"))
    )
    (net (code "96") (name "Net-(IC10A-B5)") (class "Default")
      (node (ref "IC10") (pin "14") (pinfunction "B5_14") (pintype "bidirectional"))
      (node (ref "R18") (pin "1") (pinfunction "1_1") (pintype "passive"))
    )
    (net (code "97") (name "Net-(IC10A-B6)") (class "Default")
      (node (ref "IC10") (pin "13") (pinfunction "B6_13") (pintype "bidirectional"))
      (node (ref "R19") (pin "1") (pinfunction "1_1") (pintype "passive"))
    )
    (net (code "98") (name "Net-(IC10A-B7)") (class "Default")
      (node (ref "IC10") (pin "12") (pinfunction "B7_12") (pintype "bidirectional"))
      (node (ref "R20") (pin "1") (pinfunction "1_1") (pintype "passive"))
    )
    (net (code "99") (name "Net-(IC10A-B8)") (class "Default")
      (node (ref "IC10") (pin "11") (pinfunction "B8_11") (pintype "bidirectional"))
      (node (ref "R21") (pin "1") (pinfunction "1_1") (pintype "passive"))
    )
    (net (code "100") (name "Net-(IC10A-DIR)") (class "Default")
      (node (ref "IC10") (pin "1") (pinfunction "DIR_1") (pintype "input"))
      (node (ref "IC8") (pin "3") (pinfunction "O_3") (pintype "output"))
    )
    (net (code "101") (name "Net-(Q1-B)") (class "Default")
      (node (ref "Q1") (pin "2") (pinfunction "B_2") (pintype "passive"))
      (node (ref "R3") (pin "2") (pinfunction "2_2") (pintype "passive"))
    )
    (net (code "102") (name "VCC") (class "Default")
      (node (ref "C1") (pin "1") (pinfunction "1_1") (pintype "passive"))
      (node (ref "C10") (pin "1") (pinfunction "1_1") (pintype "passive"))
      (node (ref "C2") (pin "1") (pinfunction "1_1") (pintype "passive"))
      (node (ref "C3") (pin "1") (pinfunction "1_1") (pintype "passive"))
      (node (ref "C4") (pin "1") (pinfunction "1_1") (pintype "passive"))
      (node (ref "C5") (pin "1") (pinfunction "1_1") (pintype "passive"))
      (node (ref "C6") (pin "1") (pinfunction "1_1") (pintype "passive"))
      (node (ref "C8") (pin "1") (pinfunction "1_1") (pintype "passive"))
      (node (ref "C9") (pin "1") (pinfunction "1_1") (pintype "passive"))
      (node (ref "IC4") (pin "1") (pinfunction "CLR_1") (pintype "input"))
      (node (ref "IC4") (pin "13") (pinfunction "CLR_13") (pintype "input"))
      (node (ref "IC4") (pin "4") (pinfunction "PRE_4") (pintype "input"))
      (node (ref "IC9") (pin "1") (pinfunction "DIR_1") (pintype "input"))
      (node (ref "R22") (pin "2") (pinfunction "2_2") (pintype "passive"))
      (node (ref "R23") (pin "2") (pinfunction "2_2") (pintype "passive"))
      (node (ref "ST1") (pin "B29") (pinfunction "P_B29") (pintype "bidirectional"))
    )
    (net (code "103") (name "unconnected-(IC1A-QA-Pad3)") (class "Default")
      (node (ref "IC1") (pin "3") (pinfunction "QA_3") (pintype "output"))
    )
    (net (code "104") (name "unconnected-(IC1A-QB-Pad4)") (class "Default")
      (node (ref "IC1") (pin "4") (pinfunction "QB_4") (pintype "output"))
    )
    (net (code "105") (name "unconnected-(IC4A-~{Q}-Pad6)") (class "Default")
      (node (ref "IC4") (pin "6") (pinfunction "~{Q}_6") (pintype "output"))
    )
    (net (code "106") (name "unconnected-(IC4B-~{Q}-Pad8)") (class "Default")
      (node (ref "IC4") (pin "8") (pinfunction "~{Q}_8") (pintype "output"))
    )
    (net (code "107") (name "unconnected-(IC6B-Y3-Pad5)") (class "Default")
      (node (ref "IC6") (pin "5") (pinfunction "Y3_5") (pintype "tri_state"))
    )
    (net (code "108") (name "unconnected-(ST1AA-P-PadB28)") (class "Default")
      (node (ref "ST1") (pin "B28") (pinfunction "P_B28") (pintype "bidirectional"))
    )
    (net (code "109") (name "unconnected-(ST1AB-P-PadB8)") (class "Default")
      (node (ref "ST1") (pin "B8") (pinfunction "P_B8") (pintype "bidirectional"))
    )
    (net (code "110") (name "unconnected-(ST1AL-P-PadB17)") (class "Default")
      (node (ref "ST1") (pin "B17") (pinfunction "P_B17") (pintype "bidirectional"))
    )
    (net (code "111") (name "unconnected-(ST1AM-P-PadB26)") (class "Default")
      (node (ref "ST1") (pin "B26") (pinfunction "P_B26") (pintype "bidirectional"))
    )
    (net (code "112") (name "unconnected-(ST1AN-P-PadB15)") (class "Default")
      (node (ref "ST1") (pin "B15") (pinfunction "P_B15") (pintype "bidirectional"))
    )
    (net (code "113") (name "unconnected-(ST1AO-P-PadB18)") (class "Default")
      (node (ref "ST1") (pin "B18") (pinfunction "P_B18") (pintype "bidirectional"))
    )
    (net (code "114") (name "unconnected-(ST1AP-P-PadB6)") (class "Default")
      (node (ref "ST1") (pin "B6") (pinfunction "P_B6") (pintype "bidirectional"))
    )
    (net (code "115") (name "unconnected-(ST1AQ-P-PadB16)") (class "Default")
      (node (ref "ST1") (pin "B16") (pinfunction "P_B16") (pintype "bidirectional"))
    )
    (net (code "116") (name "unconnected-(ST1AU-P-PadA1)") (class "Default")
      (node (ref "ST1") (pin "A1") (pinfunction "P_A1") (pintype "bidirectional"))
    )
    (net (code "117") (name "unconnected-(ST1AY-P-PadB25)") (class "Default")
      (node (ref "ST1") (pin "B25") (pinfunction "P_B25") (pintype "bidirectional"))
    )
    (net (code "118") (name "unconnected-(ST1AZ-P-PadB24)") (class "Default")
      (node (ref "ST1") (pin "B24") (pinfunction "P_B24") (pintype "bidirectional"))
    )
    (net (code "119") (name "unconnected-(ST1BA-P-PadB23)") (class "Default")
      (node (ref "ST1") (pin "B23") (pinfunction "P_B23") (pintype "bidirectional"))
    )
    (net (code "120") (name "unconnected-(ST1BB-P-PadB22)") (class "Default")
      (node (ref "ST1") (pin "B22") (pinfunction "P_B22") (pintype "bidirectional"))
    )
    (net (code "121") (name "unconnected-(ST1BC-P-PadB21)") (class "Default")
      (node (ref "ST1") (pin "B21") (pinfunction "P_B21") (pintype "bidirectional"))
    )
    (net (code "122") (name "unconnected-(ST1BD-P-PadB4)") (class "Default")
      (node (ref "ST1") (pin "B4") (pinfunction "P_B4") (pintype "bidirectional"))
    )
    (net (code "123") (name "unconnected-(ST1BE-P-PadB12)") (class "Default")
      (node (ref "ST1") (pin "B12") (pinfunction "P_B12") (pintype "bidirectional"))
    )
    (net (code "124") (name "unconnected-(ST1BF-P-PadB11)") (class "Default")
      (node (ref "ST1") (pin "B11") (pinfunction "P_B11") (pintype "bidirectional"))
    )
    (net (code "125") (name "unconnected-(ST1BG-P-PadB30)") (class "Default")
      (node (ref "ST1") (pin "B30") (pinfunction "P_B30") (pintype "bidirectional"))
    )
    (net (code "126") (name "unconnected-(ST1BH-P-PadB19)") (class "Default")
      (node (ref "ST1") (pin "B19") (pinfunction "P_B19") (pintype "bidirectional"))
    )
    (net (code "127") (name "unconnected-(ST1BJ-P-PadB27)") (class "Default")
      (node (ref "ST1") (pin "B27") (pinfunction "P_B27") (pintype "bidirectional"))
    )
    (net (code "128") (name "unconnected-(ST1C-P-PadB3)") (class "Default")
      (node (ref "ST1") (pin "B3") (pinfunction "P_B3") (pintype "bidirectional"))
    )
    (net (code "129") (name "unconnected-(ST1E-P-PadB5)") (class "Default")
      (node (ref "ST1") (pin "B5") (pinfunction "P_B5") (pintype "bidirectional"))
    )
    (net (code "130") (name "unconnected-(ST1H-P-PadA21)") (class "Default")
      (node (ref "ST1") (pin "A21") (pinfunction "P_A21") (pintype "bidirectional"))
    )
    (net (code "131") (name "unconnected-(ST1I-P-PadA20)") (class "Default")
      (node (ref "ST1") (pin "A20") (pinfunction "P_A20") (pintype "bidirectional"))
    )
    (net (code "132") (name "unconnected-(ST1J-P-PadA19)") (class "Default")
      (node (ref "ST1") (pin "A19") (pinfunction "P_A19") (pintype "bidirectional"))
    )
    (net (code "133") (name "unconnected-(ST1K-P-PadA18)") (class "Default")
      (node (ref "ST1") (pin "A18") (pinfunction "P_A18") (pintype "bidirectional"))
    )
    (net (code "134") (name "unconnected-(ST1L-P-PadA17)") (class "Default")
      (node (ref "ST1") (pin "A17") (pinfunction "P_A17") (pintype "bidirectional"))
    )
    (net (code "135") (name "unconnected-(ST1M-P-PadA16)") (class "Default")
      (node (ref "ST1") (pin "A16") (pinfunction "P_A16") (pintype "bidirectional"))
    )
    (net (code "136") (name "unconnected-(ST1N-P-PadA15)") (class "Default")
      (node (ref "ST1") (pin "A15") (pinfunction "P_A15") (pintype "bidirectional"))
    )
    (net (code "137") (name "unconnected-(ST1O-P-PadA14)") (class "Default")
      (node (ref "ST1") (pin "A14") (pinfunction "P_A14") (pintype "bidirectional"))
    )
    (net (code "138") (name "unconnected-(ST1P-P-PadA13)") (class "Default")
      (node (ref "ST1") (pin "A13") (pinfunction "P_A13") (pintype "bidirectional"))
    )
    (net (code "139") (name "unconnected-(ST1Q-P-PadA12)") (class "Default")
      (node (ref "ST1") (pin "A12") (pinfunction "P_A12") (pintype "bidirectional"))
    )
  )
)
